# MotorControl.net
KiCad netlist of a schematic drawn in Altium Designer
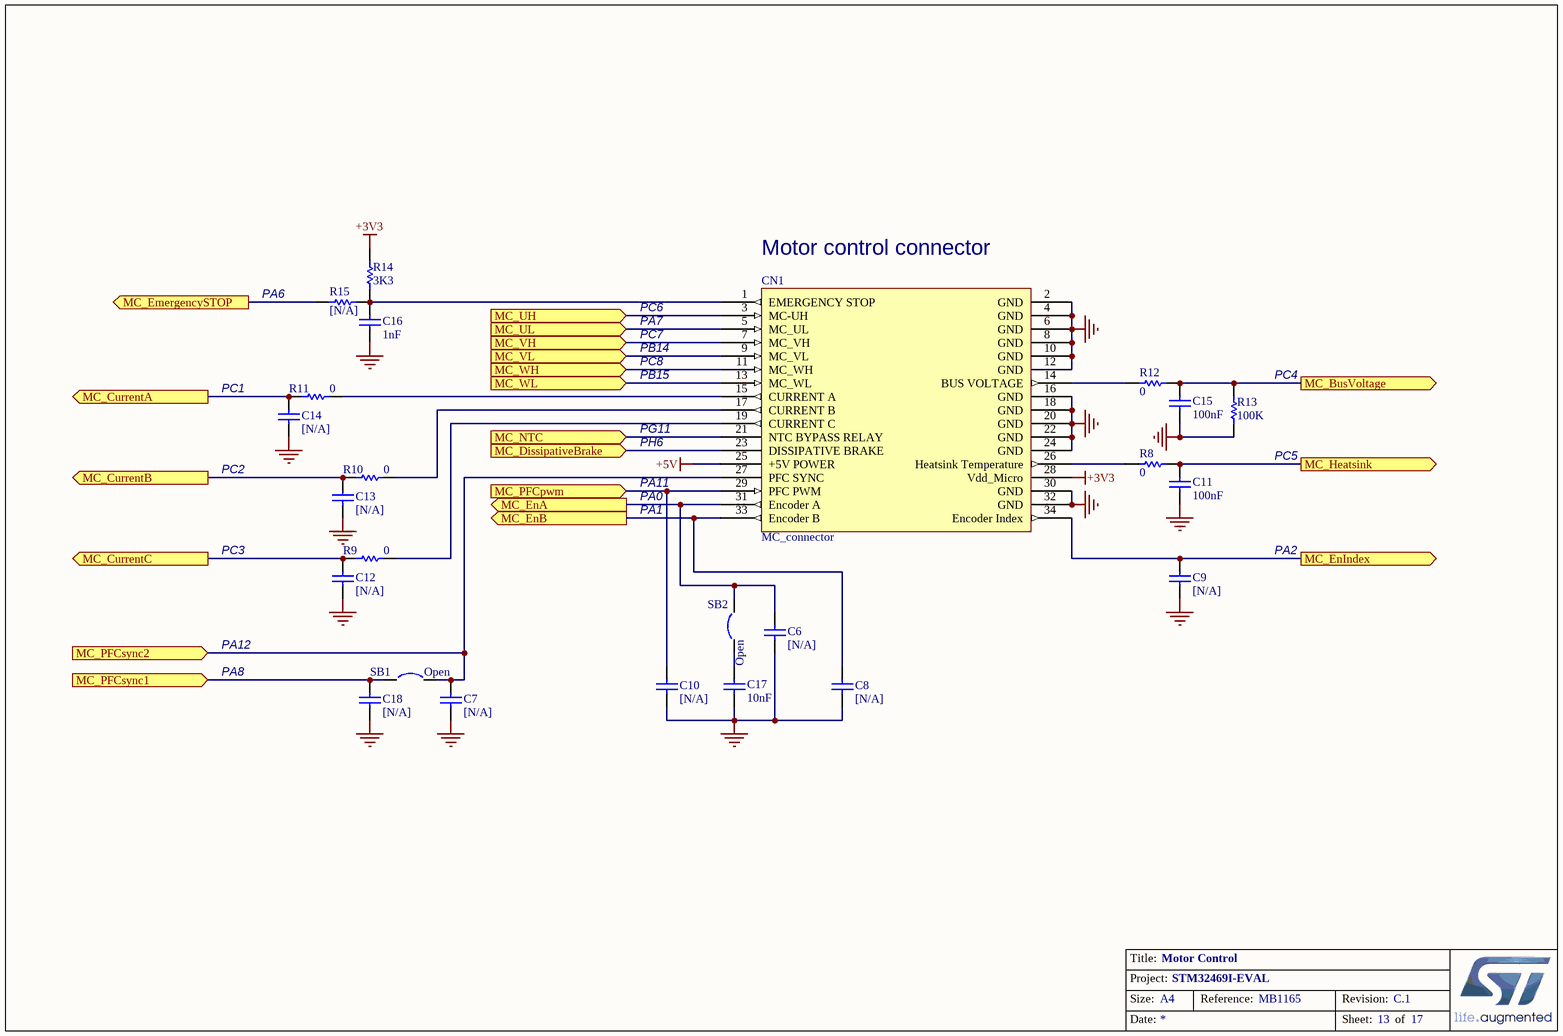
[diagram p0: MotorControl.SchDoc]

(export (version "E")
  (design (tool "Eeschema 10.0.6"))
  (components
    (comp (ref "C6")
      (value "[N/A]")
      (footprint "0603C")
      (description "Capacitor")
      (fields (field (name "PUBLISHER") "Altium Limited"))
      (libsource (lib "Miscellaneous Devices") (part "cap"))
    )
    (comp (ref "C7")
      (value "[N/A]")
      (footprint "0603C")
      (description "Capacitor")
      (fields (field (name "PUBLISHER") "Altium Limited"))
      (libsource (lib "Miscellaneous Devices") (part "cap"))
    )
    (comp (ref "C8")
      (value "[N/A]")
      (footprint "0603C")
      (description "Capacitor")
      (fields (field (name "PUBLISHER") "Altium Limited"))
      (libsource (lib "Miscellaneous Devices") (part "cap"))
    )
    (comp (ref "C9")
      (value "[N/A]")
      (footprint "0603C")
      (description "Capacitor")
      (fields (field (name "PUBLISHER") "Altium Limited"))
      (libsource (lib "Miscellaneous Devices") (part "cap"))
    )
    (comp (ref "C10")
      (value "[N/A]")
      (footprint "0603C")
      (description "Capacitor")
      (fields (field (name "PUBLISHER") "Altium Limited"))
      (libsource (lib "Miscellaneous Devices") (part "cap"))
    )
    (comp (ref "C11")
      (value "100nF")
      (footprint "0603C")
      (description "Capacitor")
      (fields (field (name "PUBLISHER") "Altium Limited"))
      (libsource (lib "Miscellaneous Devices") (part "Cap"))
    )
    (comp (ref "C12")
      (value "[N/A]")
      (footprint "0603C")
      (description "Capacitor")
      (fields (field (name "PUBLISHER") "Altium Limited"))
      (libsource (lib "Miscellaneous Devices") (part "cap"))
    )
    (comp (ref "C13")
      (value "[N/A]")
      (footprint "0603C")
      (description "Capacitor")
      (fields (field (name "PUBLISHER") "Altium Limited"))
      (libsource (lib "Miscellaneous Devices") (part "cap"))
    )
    (comp (ref "C14")
      (value "[N/A]")
      (footprint "0603C")
      (description "Capacitor")
      (fields (field (name "PUBLISHER") "Altium Limited"))
      (libsource (lib "Miscellaneous Devices") (part "cap"))
    )
    (comp (ref "C15")
      (value "100nF")
      (footprint "0603C")
      (description "Capacitor")
      (fields (field (name "PUBLISHER") "Altium Limited"))
      (libsource (lib "Miscellaneous Devices") (part "Cap"))
    )
    (comp (ref "C16")
      (value "1nF")
      (footprint "0603C")
      (description "Capacitor")
      (fields (field (name "PUBLISHER") "Altium Limited"))
      (libsource (lib "Miscellaneous Devices") (part "CAP"))
    )
    (comp (ref "C17")
      (value "10nF")
      (footprint "0603C")
      (description "Capacitor")
      (fields (field (name "PUBLISHER") "Altium Limited"))
      (libsource (lib "Miscellaneous Devices") (part "CAP"))
    )
    (comp (ref "C18")
      (value "[N/A]")
      (footprint "0603C")
      (description "Capacitor")
      (fields (field (name "PUBLISHER") "Altium Limited"))
      (libsource (lib "Miscellaneous Devices") (part "cap"))
    )
    (comp (ref "CN1")
      (value "MC_connector")
      (footprint "IDC34S")
      (libsource (lib "MB525") (part "MC_connector"))
    )
    (comp (ref "R8")
      (value "0")
      (footprint "0603R")
      (description "Resistor")
      (fields (field (name "PUBLISHER") "Altium Limited"))
      (libsource (lib "Miscellaneous Devices") (part "Res1"))
    )
    (comp (ref "R9")
      (value "0")
      (footprint "0603R")
      (description "Resistor")
      (fields (field (name "PUBLISHER") "Altium Limited"))
      (libsource (lib "Miscellaneous Devices") (part "Res1"))
    )
    (comp (ref "R10")
      (value "0")
      (footprint "0603R")
      (description "Resistor")
      (fields (field (name "PUBLISHER") "Altium Limited"))
      (libsource (lib "Miscellaneous Devices") (part "Res1"))
    )
    (comp (ref "R11")
      (value "0")
      (footprint "0603R")
      (description "Resistor")
      (fields (field (name "PUBLISHER") "Altium Limited"))
      (libsource (lib "Miscellaneous Devices") (part "Res1"))
    )
    (comp (ref "R12")
      (value "0")
      (footprint "0603R")
      (description "Resistor")
      (fields (field (name "PUBLISHER") "Altium Limited"))
      (libsource (lib "Miscellaneous Devices") (part "Res1"))
    )
    (comp (ref "R13")
      (value "100K")
      (footprint "0603R")
      (description "Resistor")
      (fields (field (name "PUBLISHER") "Altium Limited"))
      (libsource (lib "Miscellaneous Devices") (part "res1"))
    )
    (comp (ref "R14")
      (value "3K3")
      (footprint "0603R")
      (description "Resistor")
      (fields (field (name "PUBLISHER") "Altium Limited"))
      (libsource (lib "Miscellaneous Devices") (part "Res1"))
    )
    (comp (ref "R15")
      (value "[N/A]")
      (footprint "0603R")
      (description "Resistor")
      (fields (field (name "PUBLISHER") "Altium Limited"))
      (libsource (lib "Miscellaneous Devices") (part "Res1"))
    )
    (comp (ref "SB1")
      (value "Open")
      (footprint "SB_0603")
      (description "Circuit Breaker")
      (fields (field (name "PUBLISHER") "Altium Limited"))
      (libsource (lib "MB1165") (part "Circuit Breaker"))
    )
    (comp (ref "SB2")
      (value "Open")
      (footprint "SB_0603")
      (description "Circuit Breaker")
      (fields (field (name "PUBLISHER") "Altium Limited"))
      (libsource (lib "MB1165") (part "Circuit Breaker"))
    )
  )
  (nets
    (net (code "1") (name "+3V3") (class "Default")
      (node (ref "CN1") (pin "28") (pinfunction "Vdd_Micro_28") (pintype "power_in"))
      (node (ref "R14") (pin "2") (pinfunction "2_2") (pintype "passive"))
    )
    (net (code "2") (name "+5V") (class "Default")
      (node (ref "CN1") (pin "25") (pinfunction "+5V_POWER_25") (pintype "power_in"))
    )
    (net (code "3") (name "/MC_BusVoltage") (class "Default")
      (node (ref "C15") (pin "1") (pinfunction "1_1") (pintype "passive"))
      (node (ref "R12") (pin "2") (pinfunction "2_2") (pintype "passive"))
      (node (ref "R13") (pin "1") (pinfunction "1_1") (pintype "passive"))
    )
    (net (code "4") (name "/MC_CurrentA") (class "Default")
      (node (ref "C14") (pin "2") (pinfunction "2_2") (pintype "passive"))
      (node (ref "R11") (pin "1") (pinfunction "1_1") (pintype "passive"))
    )
    (net (code "5") (name "/MC_CurrentB") (class "Default")
      (node (ref "C13") (pin "2") (pinfunction "2_2") (pintype "passive"))
      (node (ref "R10") (pin "1") (pinfunction "1_1") (pintype "passive"))
    )
    (net (code "6") (name "/MC_CurrentC") (class "Default")
      (node (ref "C12") (pin "2") (pinfunction "2_2") (pintype "passive"))
      (node (ref "R9") (pin "1") (pinfunction "1_1") (pintype "passive"))
    )
    (net (code "7") (name "/MC_DissipativeBrake") (class "Default")
      (node (ref "CN1") (pin "23") (pinfunction "DISSIPATIVE_BRAKE_23") (pintype "passive"))
    )
    (net (code "8") (name "/MC_EmergencySTOP") (class "Default")
      (node (ref "R15") (pin "2") (pinfunction "2_2") (pintype "passive"))
    )
    (net (code "9") (name "/MC_EnA") (class "Default")
      (node (ref "C6") (pin "2") (pinfunction "2_2") (pintype "passive"))
      (node (ref "CN1") (pin "31") (pinfunction "Encoder_A_31") (pintype "output"))
      (node (ref "SB2") (pin "2") (pinfunction "2_2") (pintype "passive"))
    )
    (net (code "10") (name "/MC_EnB") (class "Default")
      (node (ref "C8") (pin "2") (pinfunction "2_2") (pintype "passive"))
      (node (ref "CN1") (pin "33") (pinfunction "Encoder_B_33") (pintype "output"))
    )
    (net (code "11") (name "/MC_EnIndex") (class "Default")
      (node (ref "C9") (pin "2") (pinfunction "2_2") (pintype "passive"))
      (node (ref "CN1") (pin "34") (pinfunction "Encoder_Index_34") (pintype "output"))
    )
    (net (code "12") (name "/MC_Heatsink") (class "Default")
      (node (ref "C11") (pin "1") (pinfunction "1_1") (pintype "passive"))
      (node (ref "R8") (pin "2") (pinfunction "2_2") (pintype "passive"))
    )
    (net (code "13") (name "/MC_NTC") (class "Default")
      (node (ref "CN1") (pin "21") (pinfunction "NTC_BYPASS_RELAY_21") (pintype "passive"))
    )
    (net (code "14") (name "/MC_PFCpwm") (class "Default")
      (node (ref "C10") (pin "2") (pinfunction "2_2") (pintype "passive"))
      (node (ref "CN1") (pin "29") (pinfunction "PFC_PWM_29") (pintype "input"))
    )
    (net (code "15") (name "/MC_PFCsync1") (class "Default")
      (node (ref "C18") (pin "2") (pinfunction "2_2") (pintype "passive"))
      (node (ref "SB1") (pin "1") (pinfunction "1_1") (pintype "passive"))
    )
    (net (code "16") (name "/MC_PFCsync2") (class "Default")
      (node (ref "C7") (pin "2") (pinfunction "2_2") (pintype "passive"))
      (node (ref "CN1") (pin "27") (pinfunction "PFC_SYNC_27") (pintype "passive"))
      (node (ref "SB1") (pin "2") (pinfunction "2_2") (pintype "passive"))
    )
    (net (code "17") (name "/MC_UH") (class "Default")
      (node (ref "CN1") (pin "3") (pinfunction "MC-UH_3") (pintype "input"))
    )
    (net (code "18") (name "/MC_UL") (class "Default")
      (node (ref "CN1") (pin "5") (pinfunction "MC_UL_5") (pintype "input"))
    )
    (net (code "19") (name "/MC_VH") (class "Default")
      (node (ref "CN1") (pin "7") (pinfunction "MC_VH_7") (pintype "input"))
    )
    (net (code "20") (name "/MC_VL") (class "Default")
      (node (ref "CN1") (pin "9") (pinfunction "MC_VL_9") (pintype "input"))
    )
    (net (code "21") (name "/MC_WH") (class "Default")
      (node (ref "CN1") (pin "11") (pinfunction "MC_WH_11") (pintype "input"))
    )
    (net (code "22") (name "/MC_WL") (class "Default")
      (node (ref "CN1") (pin "13") (pinfunction "MC_WL_13") (pintype "input"))
    )
    (net (code "23") (name "GND") (class "Default")
      (node (ref "C10") (pin "1") (pinfunction "1_1") (pintype "passive"))
      (node (ref "C11") (pin "2") (pinfunction "2_2") (pintype "passive"))
      (node (ref "C12") (pin "1") (pinfunction "1_1") (pintype "passive"))
      (node (ref "C13") (pin "1") (pinfunction "1_1") (pintype "passive"))
      (node (ref "C14") (pin "1") (pinfunction "1_1") (pintype "passive"))
      (node (ref "C15") (pin "2") (pinfunction "2_2") (pintype "passive"))
      (node (ref "C16") (pin "1") (pinfunction "1_1") (pintype "passive"))
      (node (ref "C17") (pin "2") (pinfunction "2_2") (pintype "passive"))
      (node (ref "C18") (pin "1") (pinfunction "1_1") (pintype "passive"))
      (node (ref "C6") (pin "1") (pinfunction "1_1") (pintype "passive"))
      (node (ref "C7") (pin "1") (pinfunction "1_1") (pintype "passive"))
      (node (ref "C8") (pin "1") (pinfunction "1_1") (pintype "passive"))
      (node (ref "C9") (pin "1") (pinfunction "1_1") (pintype "passive"))
      (node (ref "CN1") (pin "10") (pinfunction "GND_10") (pintype "power_in"))
      (node (ref "CN1") (pin "12") (pinfunction "GND_12") (pintype "power_in"))
      (node (ref "CN1") (pin "16") (pinfunction "GND_16") (pintype "power_in"))
      (node (ref "CN1") (pin "18") (pinfunction "GND_18") (pintype "power_in"))
      (node (ref "CN1") (pin "2") (pinfunction "GND_2") (pintype "power_in"))
      (node (ref "CN1") (pin "20") (pinfunction "GND_20") (pintype "power_in"))
      (node (ref "CN1") (pin "22") (pinfunction "GND_22") (pintype "power_in"))
      (node (ref "CN1") (pin "24") (pinfunction "GND_24") (pintype "power_in"))
      (node (ref "CN1") (pin "30") (pinfunction "GND_30") (pintype "power_in"))
      (node (ref "CN1") (pin "32") (pinfunction "GND_32") (pintype "power_in"))
      (node (ref "CN1") (pin "4") (pinfunction "GND_4") (pintype "power_in"))
      (node (ref "CN1") (pin "6") (pinfunction "GND_6") (pintype "power_in"))
      (node (ref "CN1") (pin "8") (pinfunction "GND_8") (pintype "power_in"))
      (node (ref "R13") (pin "2") (pinfunction "2_2") (pintype "passive"))
    )
    (net (code "24") (name "Net-(C17-Pad1)") (class "Default")
      (node (ref "C17") (pin "1") (pinfunction "1_1") (pintype "passive"))
      (node (ref "SB2") (pin "1") (pinfunction "1_1") (pintype "passive"))
    )
    (net (code "25") (name "Net-(CN1-BUS_VOLTAGE)") (class "Default")
      (node (ref "CN1") (pin "14") (pinfunction "BUS_VOLTAGE_14") (pintype "output"))
      (node (ref "R12") (pin "1") (pinfunction "1_1") (pintype "passive"))
    )
    (net (code "26") (name "Net-(CN1-CURRENT_A)") (class "Default")
      (node (ref "CN1") (pin "15") (pinfunction "CURRENT_A_15") (pintype "output"))
      (node (ref "R11") (pin "2") (pinfunction "2_2") (pintype "passive"))
    )
    (net (code "27") (name "Net-(CN1-CURRENT_B)") (class "Default")
      (node (ref "CN1") (pin "17") (pinfunction "CURRENT_B_17") (pintype "output"))
      (node (ref "R10") (pin "2") (pinfunction "2_2") (pintype "passive"))
    )
    (net (code "28") (name "Net-(CN1-CURRENT_C)") (class "Default")
      (node (ref "CN1") (pin "19") (pinfunction "CURRENT_C_19") (pintype "output"))
      (node (ref "R9") (pin "2") (pinfunction "2_2") (pintype "passive"))
    )
    (net (code "29") (name "Net-(CN1-EMERGENCY_STOP)") (class "Default")
      (node (ref "C16") (pin "2") (pinfunction "2_2") (pintype "passive"))
      (node (ref "CN1") (pin "1") (pinfunction "EMERGENCY_STOP_1") (pintype "output"))
      (node (ref "R14") (pin "1") (pinfunction "1_1") (pintype "passive"))
      (node (ref "R15") (pin "1") (pinfunction "1_1") (pintype "passive"))
    )
    (net (code "30") (name "Net-(CN1-Heatsink_Temperature)") (class "Default")
      (node (ref "CN1") (pin "26") (pinfunction "Heatsink_Temperature_26") (pintype "output"))
      (node (ref "R8") (pin "1") (pinfunction "1_1") (pintype "passive"))
    )
  )
)
